# Limiter.net
KiCad netlist of a schematic drawn in Altium Designer
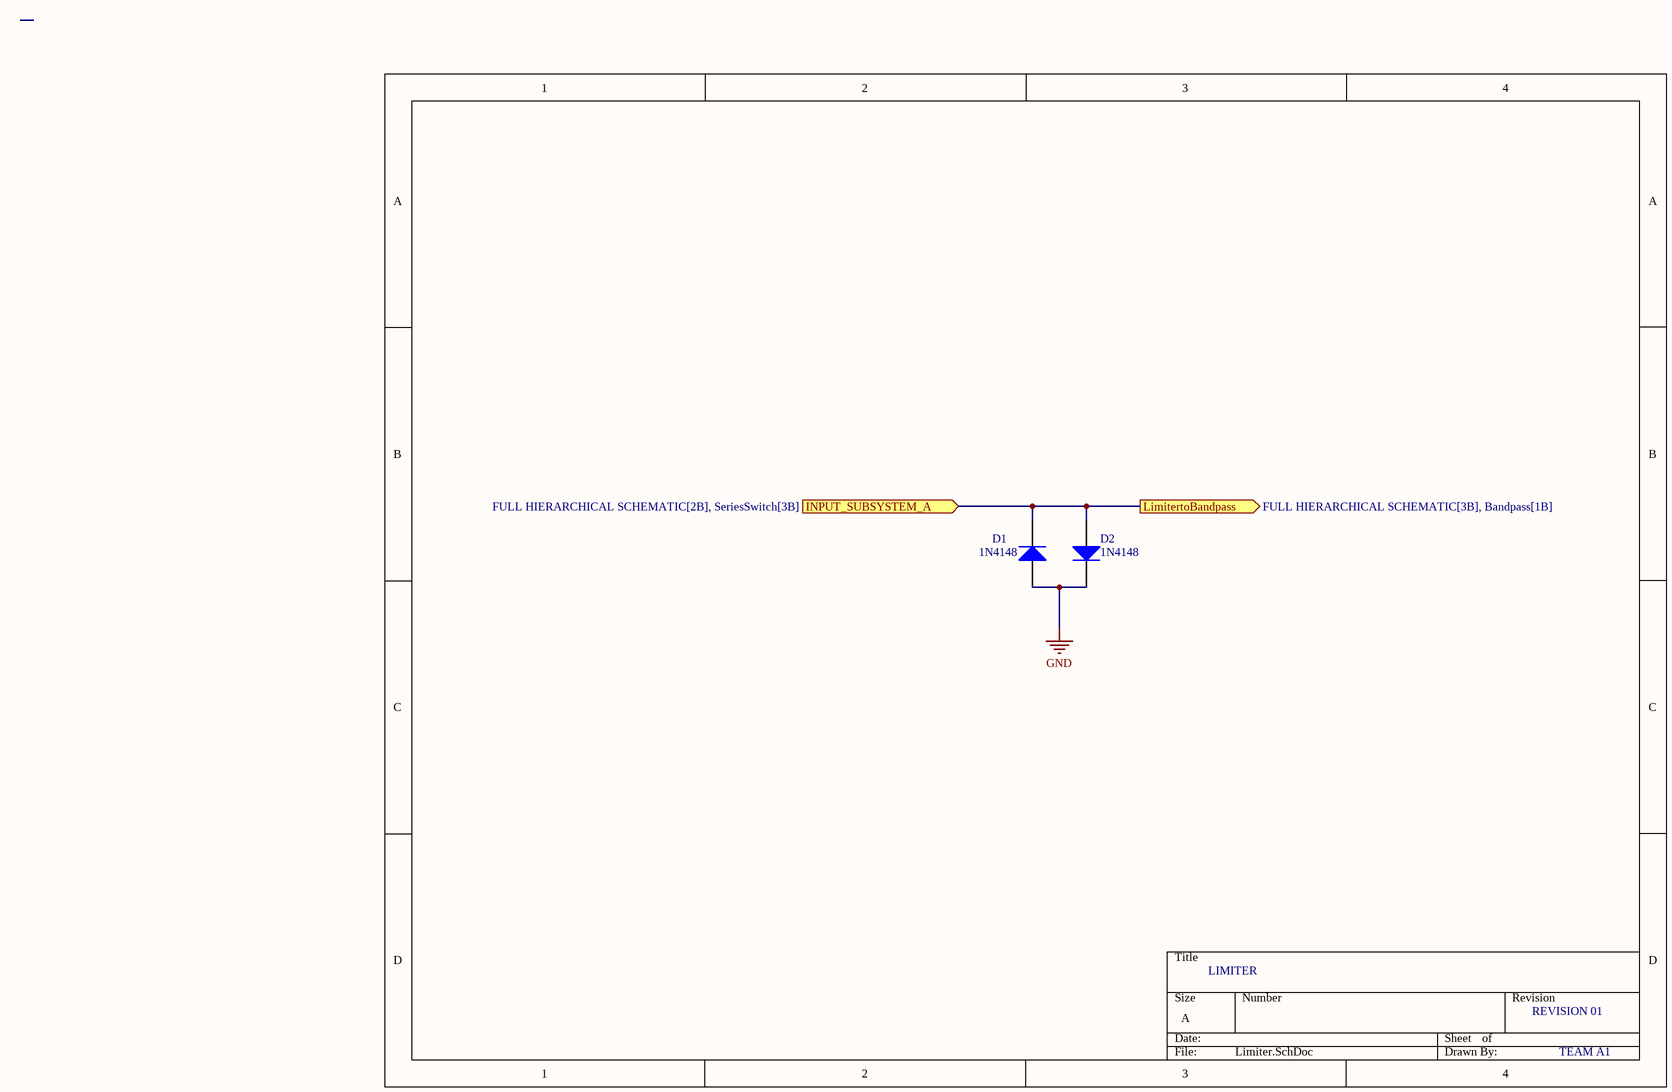
[diagram p0: Limiter.SchDoc]

(export (version "E")
  (design (tool "Eeschema 10.0.6"))
  (components
    (comp (ref "D1")
      (value "1N4148")
      (footprint "NXP-SOD27-2_V")
      (description "High-speed Diode, 100 V, 450 mA, 2-Pin SOD27, RoHS")
      (fields (field (name "MANUFACTURER") "NXP Semiconductors"))
      (libsource (lib "Altium Content Vault") (part "NXP-A1K2-2"))
    )
    (comp (ref "D2")
      (value "1N4148")
      (footprint "NXP-SOD27-2_V")
      (description "High-speed Diode, 100 V, 450 mA, 2-Pin SOD27, RoHS")
      (fields (field (name "MANUFACTURER") "NXP Semiconductors"))
      (libsource (lib "Altium Content Vault") (part "NXP-A1K2-2"))
    )
  )
  (nets
    (net (code "1") (name "/INPUT_SUBSYSTEM_A") (class "Default")
      (node (ref "D1") (pin "2") (pinfunction "K_2") (pintype "passive"))
      (node (ref "D2") (pin "1") (pinfunction "A_1") (pintype "passive"))
    )
    (net (code "2") (name "GND") (class "Default")
      (node (ref "D1") (pin "1") (pinfunction "A_1") (pintype "passive"))
      (node (ref "D2") (pin "2") (pinfunction "K_2") (pintype "passive"))
    )
  )
)
